# S7_Audio.net
KiCad netlist of a schematic drawn in Altium Designer
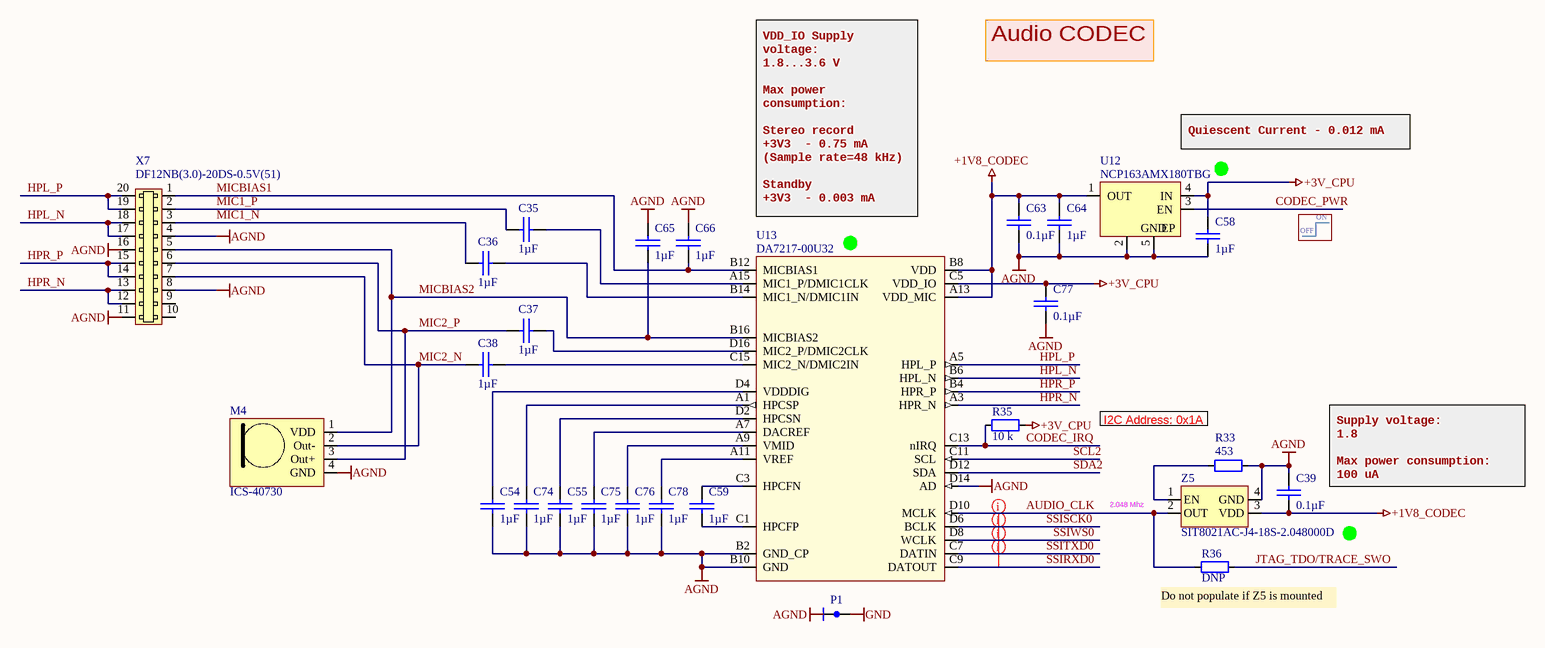
[diagram p0: S7_Audio.SchDoc]

(export (version "E")
  (design (tool "Eeschema 10.0.6"))
  (components
    (comp (ref "C35")
      (value "1µF")
      (footprint "0402 CAP")
      (description "1µF, ±20%, 25V, X5R, 0402 (1005 Metric), -55°C ~ 85°C, -, General Purpose")
      (fields (field (name "PART NUMBER") "TMK105BJ105MV-F") (field (name "MANUFACTURER") "Taiyo Yuden"))
      (libsource (lib "ea_PassivComps") (part "Capacitor"))
    )
    (comp (ref "C36")
      (value "1µF")
      (footprint "0402 CAP")
      (description "1µF, ±20%, 25V, X5R, 0402 (1005 Metric), -55°C ~ 85°C, -, General Purpose")
      (fields (field (name "PART NUMBER") "TMK105BJ105MV-F") (field (name "MANUFACTURER") "Taiyo Yuden"))
      (libsource (lib "ea_PassivComps") (part "Capacitor"))
    )
    (comp (ref "C37")
      (value "1µF")
      (footprint "0402 CAP")
      (description "1µF, ±20%, 25V, X5R, 0402 (1005 Metric), -55°C ~ 85°C, -, General Purpose")
      (fields (field (name "PART NUMBER") "TMK105BJ105MV-F") (field (name "MANUFACTURER") "Taiyo Yuden"))
      (libsource (lib "ea_PassivComps") (part "Capacitor"))
    )
    (comp (ref "C38")
      (value "1µF")
      (footprint "0402 CAP")
      (description "1µF, ±20%, 25V, X5R, 0402 (1005 Metric), -55°C ~ 85°C, -, General Purpose")
      (fields (field (name "PART NUMBER") "TMK105BJ105MV-F") (field (name "MANUFACTURER") "Taiyo Yuden"))
      (libsource (lib "ea_PassivComps") (part "Capacitor"))
    )
    (comp (ref "C39")
      (value "0.1µF")
      (footprint "0402 CAP")
      (description "0.1µF, ±10%, 50V, X7R, 0402 (1005 Metric), -55°C ~ 125°C, -, General Purpose")
      (fields
        (field (name "PART NUMBER") "0402B104K500CT")
        (field (name "MANUFACTURER") "Walsin Technology Corporation")
      )
      (libsource (lib "ea_PassivComps") (part "Capacitor"))
    )
    (comp (ref "C54")
      (value "1µF")
      (footprint "0402 CAP")
      (description "1µF, ±20%, 25V, X5R, 0402 (1005 Metric), -55°C ~ 85°C, -, General Purpose")
      (fields (field (name "PART NUMBER") "TMK105BJ105MV-F") (field (name "MANUFACTURER") "Taiyo Yuden"))
      (libsource (lib "ea_PassivComps") (part "Capacitor"))
    )
    (comp (ref "C55")
      (value "1µF")
      (footprint "0402 CAP")
      (description "1µF, ±20%, 25V, X5R, 0402 (1005 Metric), -55°C ~ 85°C, -, General Purpose")
      (fields (field (name "PART NUMBER") "TMK105BJ105MV-F") (field (name "MANUFACTURER") "Taiyo Yuden"))
      (libsource (lib "ea_PassivComps") (part "Capacitor"))
    )
    (comp (ref "C58")
      (value "1µF")
      (footprint "0402 CAP")
      (description "1µF, ±20%, 25V, X5R, 0402 (1005 Metric), -55°C ~ 85°C, -, General Purpose")
      (fields (field (name "PART NUMBER") "TMK105BJ105MV-F") (field (name "MANUFACTURER") "Taiyo Yuden"))
      (libsource (lib "ea_PassivComps") (part "Capacitor"))
    )
    (comp (ref "C59")
      (value "1µF")
      (footprint "0402 CAP")
      (description "1µF, ±20%, 25V, X5R, 0402 (1005 Metric), -55°C ~ 85°C, -, General Purpose")
      (fields (field (name "PART NUMBER") "TMK105BJ105MV-F") (field (name "MANUFACTURER") "Taiyo Yuden"))
      (libsource (lib "ea_PassivComps") (part "Capacitor"))
    )
    (comp (ref "C63")
      (value "0.1µF")
      (footprint "0402 CAP")
      (description "0.1µF, ±10%, 50V, X7R, 0402 (1005 Metric), -55°C ~ 125°C, -, General Purpose")
      (fields
        (field (name "PART NUMBER") "0402B104K500CT")
        (field (name "MANUFACTURER") "Walsin Technology Corporation")
      )
      (libsource (lib "ea_PassivComps") (part "Capacitor"))
    )
    (comp (ref "C64")
      (value "1µF")
      (footprint "0402 CAP")
      (description "1µF, ±20%, 25V, X5R, 0402 (1005 Metric), -55°C ~ 85°C, -, General Purpose")
      (fields (field (name "PART NUMBER") "TMK105BJ105MV-F") (field (name "MANUFACTURER") "Taiyo Yuden"))
      (libsource (lib "ea_PassivComps") (part "Capacitor"))
    )
    (comp (ref "C65")
      (value "1µF")
      (footprint "0402 CAP")
      (description "1µF, ±20%, 25V, X5R, 0402 (1005 Metric), -55°C ~ 85°C, -, General Purpose")
      (fields (field (name "PART NUMBER") "TMK105BJ105MV-F") (field (name "MANUFACTURER") "Taiyo Yuden"))
      (libsource (lib "ea_PassivComps") (part "Capacitor"))
    )
    (comp (ref "C66")
      (value "1µF")
      (footprint "0402 CAP")
      (description "1µF, ±20%, 25V, X5R, 0402 (1005 Metric), -55°C ~ 85°C, -, General Purpose")
      (fields (field (name "PART NUMBER") "TMK105BJ105MV-F") (field (name "MANUFACTURER") "Taiyo Yuden"))
      (libsource (lib "ea_PassivComps") (part "Capacitor"))
    )
    (comp (ref "C74")
      (value "1µF")
      (footprint "0402 CAP")
      (description "1µF, ±20%, 25V, X5R, 0402 (1005 Metric), -55°C ~ 85°C, -, General Purpose")
      (fields (field (name "PART NUMBER") "TMK105BJ105MV-F") (field (name "MANUFACTURER") "Taiyo Yuden"))
      (libsource (lib "ea_PassivComps") (part "Capacitor"))
    )
    (comp (ref "C75")
      (value "1µF")
      (footprint "0402 CAP")
      (description "1µF, ±20%, 25V, X5R, 0402 (1005 Metric), -55°C ~ 85°C, -, General Purpose")
      (fields (field (name "PART NUMBER") "TMK105BJ105MV-F") (field (name "MANUFACTURER") "Taiyo Yuden"))
      (libsource (lib "ea_PassivComps") (part "Capacitor"))
    )
    (comp (ref "C76")
      (value "1µF")
      (footprint "0402 CAP")
      (description "1µF, ±20%, 25V, X5R, 0402 (1005 Metric), -55°C ~ 85°C, -, General Purpose")
      (fields (field (name "PART NUMBER") "TMK105BJ105MV-F") (field (name "MANUFACTURER") "Taiyo Yuden"))
      (libsource (lib "ea_PassivComps") (part "Capacitor"))
    )
    (comp (ref "C77")
      (value "0.1µF")
      (footprint "0402 CAP")
      (description "0.1µF, ±10%, 50V, X7R, 0402 (1005 Metric), -55°C ~ 125°C, -, General Purpose")
      (fields
        (field (name "PART NUMBER") "0402B104K500CT")
        (field (name "MANUFACTURER") "Walsin Technology Corporation")
      )
      (libsource (lib "ea_PassivComps") (part "Capacitor"))
    )
    (comp (ref "C78")
      (value "1µF")
      (footprint "0402 CAP")
      (description "1µF, ±20%, 25V, X5R, 0402 (1005 Metric), -55°C ~ 85°C, -, General Purpose")
      (fields (field (name "PART NUMBER") "TMK105BJ105MV-F") (field (name "MANUFACTURER") "Taiyo Yuden"))
      (libsource (lib "ea_PassivComps") (part "Capacitor"))
    )
    (comp (ref "M4")
      (value "ICS-40730")
      (footprint "ICS-40730")
      (fields (field (name "MANUFACTURER") "TDK InvenSense") (field (name "PARTNUM") "1428-1141-1-ND"))
      (libsource (lib "ea_Sound_devices") (part "ICS-40730"))
    )
    (comp (ref "P1")
      (value "Net tie 0.1mm")
      (footprint "Net tee 0.1 mm")
      (libsource (lib "ea_Mechanical") (part "Net tie 0.1mm"))
    )
    (comp (ref "R33")
      (value "453")
      (footprint "0402")
      (fields
        (field (name "MANUFACTURER") "Stackpole Electronics Inc")
        (field (name "TOLERANCE") "±1%")
        (field (name "VOLTAGE") "75V")
      )
      (libsource (lib "ea_PassivComps") (part "Resistor"))
    )
    (comp (ref "R35")
      (value "10 k")
      (footprint "0402")
      (fields
        (field (name "MANUFACTURER") "Stackpole Electronics Inc")
        (field (name "TOLERANCE") "±1%")
        (field (name "VOLTAGE") "75V")
      )
      (libsource (lib "") (part "Resistor_1"))
    )
    (comp (ref "R36")
      (value "DNP")
      (footprint "0402")
      (fields (field (name "Comment") "Resistor"))
      (libsource (lib "ea_PassivComps") (part "Resistor"))
    )
    (comp (ref "U12")
      (value "NCP163AMX180TBG")
      (footprint "4-XDFN")
      (description "LDO 1.8V, 250 mA, Vin < 5.5V, Iq < 20uA, -40..+125 C,  4-XDFN (1x1)")
      (fields
        (field (name "MANUFACTURER") "ON Semiconductor")
        (field (name "PARTNUM") "NCP163AMX180TBGOSCT-ND")
      )
      (libsource (lib "ea_IC_Linear_reg_LDO") (part "NCP163AMX180TBG"))
    )
    (comp (ref "U13")
      (value "DA7217-00U32")
      (footprint "Dilaog 34-WLCSP (4.57x1.98)")
      (description "Low power CODEC, 24 b, 2/2, I²C, I²S,  1.5V ~ 3.6V,  -25°C ~ 85°C, 34-WLCSP (4.57x1.98)")
      (fields
        (field (name "MANUFACTURER") "Dialog Semiconductor GmbH")
        (field (name "PARTNUM") "1564-1043-1-ND")
      )
      (libsource (lib "ea_IC_audio") (part "DA7217-00U32"))
    )
    (comp (ref "X7")
      (value "DF12NB(3.0)-20DS-0.5V(51)")
      (footprint "DF12NB(3.0)-20DS-0.5V(51)")
      (fields
        (field (name "MANUFACTURER") "Hirose Electric")
        (field (name "PARTNUM") "26-DF12NB(3.0)-20DS-0.5V(51)CT-ND - Cut Tape (CT)")
      )
      (libsource (lib "ea_Connectors_0.5_mm_pitch") (part "DF12NB(3.0)-20DS-0.5V(51)"))
    )
    (comp (ref "Z5")
      (value "SIT8021AC-J4-18S-2.048000D")
      (footprint "SiT8021")
      (description "2.048MHz XO (Standard) LVCMOS Oscillator 1.8V Standby (Power Down) 4-UFBGA, CSPBGA, -20...+70 C")
      (fields (field (name "MANUFACTURER") "SiTIME"))
      (libsource (lib "ea_OSC_CLK_GEN") (part "SIT8021AC-J4-18S-2.048000D"))
    )
  )
  (nets
    (net (code "1") (name "+1V8_CODEC") (class "Default")
      (node (ref "C39") (pin "2") (pinfunction "2_2") (pintype "passive"))
      (node (ref "C63") (pin "1") (pinfunction "1_1") (pintype "passive"))
      (node (ref "C64") (pin "1") (pinfunction "1_1") (pintype "passive"))
      (node (ref "U12") (pin "1") (pinfunction "OUT_1") (pintype "power_in"))
      (node (ref "U13") (pin "A13") (pinfunction "VDD_MIC_A13") (pintype "power_in"))
      (node (ref "U13") (pin "B8") (pinfunction "VDD_B8") (pintype "power_in"))
      (node (ref "Z5") (pin "3") (pinfunction "VDD_3") (pintype "passive"))
    )
    (net (code "2") (name "+3V_CPU") (class "Default")
      (node (ref "C58") (pin "1") (pinfunction "1_1") (pintype "passive"))
      (node (ref "C77") (pin "1") (pinfunction "1_1") (pintype "passive"))
      (node (ref "R35") (pin "2") (pinfunction "2_2") (pintype "passive"))
      (node (ref "U12") (pin "4") (pinfunction "IN_4") (pintype "power_in"))
      (node (ref "U13") (pin "C5") (pinfunction "VDD_IO_C5") (pintype "power_in"))
    )
    (net (code "3") (name "/AUDIO_CLK") (class "Default")
      (node (ref "R36") (pin "2") (pinfunction "2_2") (pintype "passive"))
      (node (ref "U13") (pin "D10") (pinfunction "MCLK_D10") (pintype "input"))
      (node (ref "Z5") (pin "2") (pinfunction "OUT_2") (pintype "passive"))
    )
    (net (code "4") (name "/CODEC_IRQ") (class "Default")
      (node (ref "R35") (pin "1") (pinfunction "1_1") (pintype "passive"))
      (node (ref "U13") (pin "C13") (pinfunction "nIRQ_C13") (pintype "bidirectional"))
    )
    (net (code "5") (name "/CODEC_PWR") (class "Default")
      (node (ref "U12") (pin "3") (pinfunction "EN_3") (pintype "power_in"))
    )
    (net (code "6") (name "/HPL_N") (class "Default")
      (node (ref "U13") (pin "B6") (pinfunction "HPL_N_B6") (pintype "output"))
      (node (ref "X7") (pin "17") (pinfunction "9_17") (pintype "passive"))
      (node (ref "X7") (pin "18") (pinfunction "10_18") (pintype "passive"))
    )
    (net (code "7") (name "/HPL_P") (class "Default")
      (node (ref "U13") (pin "A5") (pinfunction "HPL_P_A5") (pintype "output"))
      (node (ref "X7") (pin "19") (pinfunction "10_19") (pintype "passive"))
      (node (ref "X7") (pin "20") (pinfunction "11_20") (pintype "passive"))
    )
    (net (code "8") (name "/HPR_N") (class "Default")
      (node (ref "U13") (pin "A3") (pinfunction "HPR_N_A3") (pintype "output"))
      (node (ref "X7") (pin "12") (pinfunction "7_12") (pintype "passive"))
      (node (ref "X7") (pin "13") (pinfunction "7_13") (pintype "passive"))
    )
    (net (code "9") (name "/HPR_P") (class "Default")
      (node (ref "U13") (pin "B4") (pinfunction "HPR_P_B4") (pintype "output"))
      (node (ref "X7") (pin "14") (pinfunction "8_14") (pintype "passive"))
      (node (ref "X7") (pin "15") (pinfunction "8_15") (pintype "passive"))
    )
    (net (code "10") (name "/JTAG_TDO{slash}TRACE_SWO") (class "Default")
      (node (ref "R36") (pin "1") (pinfunction "1_1") (pintype "passive"))
    )
    (net (code "11") (name "/MIC1_N") (class "Default")
      (node (ref "C36") (pin "1") (pinfunction "1_1") (pintype "passive"))
      (node (ref "X7") (pin "3") (pinfunction "2_3") (pintype "passive"))
    )
    (net (code "12") (name "/MIC1_P") (class "Default")
      (node (ref "C35") (pin "1") (pinfunction "1_1") (pintype "passive"))
      (node (ref "X7") (pin "2") (pinfunction "2_2") (pintype "passive"))
    )
    (net (code "13") (name "/MIC2_N") (class "Default")
      (node (ref "C38") (pin "1") (pinfunction "1_1") (pintype "passive"))
      (node (ref "M4") (pin "2") (pinfunction "Out-_2") (pintype "passive"))
      (node (ref "X7") (pin "7") (pinfunction "4_7") (pintype "passive"))
    )
    (net (code "14") (name "/MIC2_P") (class "Default")
      (node (ref "C37") (pin "1") (pinfunction "1_1") (pintype "passive"))
      (node (ref "M4") (pin "3") (pinfunction "Out+_3") (pintype "passive"))
      (node (ref "X7") (pin "6") (pinfunction "4_6") (pintype "passive"))
    )
    (net (code "15") (name "/MICBIAS1") (class "Default")
      (node (ref "C66") (pin "2") (pinfunction "2_2") (pintype "passive"))
      (node (ref "U13") (pin "B12") (pinfunction "MICBIAS1_B12") (pintype "bidirectional"))
      (node (ref "X7") (pin "1") (pinfunction "1_1") (pintype "passive"))
    )
    (net (code "16") (name "/MICBIAS2") (class "Default")
      (node (ref "C65") (pin "2") (pinfunction "2_2") (pintype "passive"))
      (node (ref "M4") (pin "1") (pinfunction "VDD_1") (pintype "passive"))
      (node (ref "U13") (pin "B16") (pinfunction "MICBIAS2_B16") (pintype "bidirectional"))
      (node (ref "X7") (pin "5") (pinfunction "3_5") (pintype "passive"))
    )
    (net (code "17") (name "/SCL2") (class "Default")
      (node (ref "U13") (pin "C11") (pinfunction "SCL_C11") (pintype "input"))
    )
    (net (code "18") (name "/SDA2") (class "Default")
      (node (ref "U13") (pin "D12") (pinfunction "SDA_D12") (pintype "bidirectional"))
    )
    (net (code "19") (name "/SSIRXD0") (class "Default")
      (node (ref "U13") (pin "C9") (pinfunction "DATOUT_C9") (pintype "bidirectional"))
    )
    (net (code "20") (name "/SSISCK0") (class "Default")
      (node (ref "U13") (pin "D6") (pinfunction "BCLK_D6") (pintype "bidirectional"))
    )
    (net (code "21") (name "/SSITXD0") (class "Default")
      (node (ref "U13") (pin "C7") (pinfunction "DATIN_C7") (pintype "bidirectional"))
    )
    (net (code "22") (name "/SSIWS0") (class "Default")
      (node (ref "U13") (pin "D8") (pinfunction "WCLK_D8") (pintype "bidirectional"))
    )
    (net (code "23") (name "AGND") (class "Default")
      (node (ref "C39") (pin "1") (pinfunction "1_1") (pintype "passive"))
      (node (ref "C54") (pin "2") (pinfunction "2_2") (pintype "passive"))
      (node (ref "C55") (pin "2") (pinfunction "2_2") (pintype "passive"))
      (node (ref "C58") (pin "2") (pinfunction "2_2") (pintype "passive"))
      (node (ref "C63") (pin "2") (pinfunction "2_2") (pintype "passive"))
      (node (ref "C64") (pin "2") (pinfunction "2_2") (pintype "passive"))
      (node (ref "C65") (pin "1") (pinfunction "1_1") (pintype "passive"))
      (node (ref "C66") (pin "1") (pinfunction "1_1") (pintype "passive"))
      (node (ref "C74") (pin "2") (pinfunction "2_2") (pintype "passive"))
      (node (ref "C75") (pin "2") (pinfunction "2_2") (pintype "passive"))
      (node (ref "C76") (pin "2") (pinfunction "2_2") (pintype "passive"))
      (node (ref "C77") (pin "2") (pinfunction "2_2") (pintype "passive"))
      (node (ref "C78") (pin "2") (pinfunction "2_2") (pintype "passive"))
      (node (ref "M4") (pin "4") (pinfunction "GND_4") (pintype "passive"))
      (node (ref "P1") (pin "1") (pinfunction "1_1") (pintype "passive"))
      (node (ref "R33") (pin "1") (pinfunction "1_1") (pintype "passive"))
      (node (ref "U12") (pin "2") (pinfunction "GND_2") (pintype "power_in"))
      (node (ref "U12") (pin "5") (pinfunction "EP_5") (pintype "power_in"))
      (node (ref "U13") (pin "B10") (pinfunction "GND_B10") (pintype "power_in"))
      (node (ref "U13") (pin "B2") (pinfunction "GND_CP_B2") (pintype "power_in"))
      (node (ref "U13") (pin "D14") (pinfunction "AD_D14") (pintype "input"))
      (node (ref "X7") (pin "11") (pinfunction "6_11") (pintype "passive"))
      (node (ref "X7") (pin "16") (pinfunction "9_16") (pintype "passive"))
      (node (ref "X7") (pin "4") (pinfunction "3_4") (pintype "passive"))
      (node (ref "X7") (pin "8") (pinfunction "5_8") (pintype "passive"))
      (node (ref "Z5") (pin "4") (pinfunction "GND_4") (pintype "passive"))
    )
    (net (code "24") (name "GND") (class "Default")
      (node (ref "P1") (pin "2") (pinfunction "2_2") (pintype "passive"))
    )
    (net (code "25") (name "Net-(U13-DACREF)") (class "Default")
      (node (ref "C75") (pin "1") (pinfunction "1_1") (pintype "passive"))
      (node (ref "U13") (pin "A7") (pinfunction "DACREF_A7") (pintype "power_in"))
    )
    (net (code "26") (name "Net-(U13-HPCFN)") (class "Default")
      (node (ref "C59") (pin "1") (pinfunction "1_1") (pintype "passive"))
      (node (ref "U13") (pin "C3") (pinfunction "HPCFN_C3") (pintype "bidirectional"))
    )
    (net (code "27") (name "Net-(U13-HPCFP)") (class "Default")
      (node (ref "C59") (pin "2") (pinfunction "2_2") (pintype "passive"))
      (node (ref "U13") (pin "C1") (pinfunction "HPCFP_C1") (pintype "bidirectional"))
    )
    (net (code "28") (name "Net-(U13-HPCSN)") (class "Default")
      (node (ref "C55") (pin "1") (pinfunction "1_1") (pintype "passive"))
      (node (ref "U13") (pin "D2") (pinfunction "HPCSN_D2") (pintype "bidirectional"))
    )
    (net (code "29") (name "Net-(U13-HPCSP)") (class "Default")
      (node (ref "C74") (pin "1") (pinfunction "1_1") (pintype "passive"))
      (node (ref "U13") (pin "A1") (pinfunction "HPCSP_A1") (pintype "output"))
    )
    (net (code "30") (name "Net-(U13-MIC1_N{slash}DMIC1IN)") (class "Default")
      (node (ref "C36") (pin "2") (pinfunction "2_2") (pintype "passive"))
      (node (ref "U13") (pin "B14") (pinfunction "MIC1_N/DMIC1IN_B14") (pintype "bidirectional"))
    )
    (net (code "31") (name "Net-(U13-MIC1_P{slash}DMIC1CLK)") (class "Default")
      (node (ref "C35") (pin "2") (pinfunction "2_2") (pintype "passive"))
      (node (ref "U13") (pin "A15") (pinfunction "MIC1_P/DMIC1CLK_A15") (pintype "bidirectional"))
    )
    (net (code "32") (name "Net-(U13-MIC2_N{slash}DMIC2IN)") (class "Default")
      (node (ref "C38") (pin "2") (pinfunction "2_2") (pintype "passive"))
      (node (ref "U13") (pin "C15") (pinfunction "MIC2_N/DMIC2IN_C15") (pintype "bidirectional"))
    )
    (net (code "33") (name "Net-(U13-MIC2_P{slash}DMIC2CLK)") (class "Default")
      (node (ref "C37") (pin "2") (pinfunction "2_2") (pintype "passive"))
      (node (ref "U13") (pin "D16") (pinfunction "MIC2_P/DMIC2CLK_D16") (pintype "bidirectional"))
    )
    (net (code "34") (name "Net-(U13-VDDDIG)") (class "Default")
      (node (ref "C54") (pin "1") (pinfunction "1_1") (pintype "passive"))
      (node (ref "U13") (pin "D4") (pinfunction "VDDDIG_D4") (pintype "power_in"))
    )
    (net (code "35") (name "Net-(U13-VMID)") (class "Default")
      (node (ref "C76") (pin "1") (pinfunction "1_1") (pintype "passive"))
      (node (ref "U13") (pin "A9") (pinfunction "VMID_A9") (pintype "power_in"))
    )
    (net (code "36") (name "Net-(U13-VREF)") (class "Default")
      (node (ref "C78") (pin "1") (pinfunction "1_1") (pintype "passive"))
      (node (ref "U13") (pin "A11") (pinfunction "VREF_A11") (pintype "power_in"))
    )
    (net (code "37") (name "Net-(Z5-EN)") (class "Default")
      (node (ref "R33") (pin "2") (pinfunction "2_2") (pintype "passive"))
      (node (ref "Z5") (pin "1") (pinfunction "EN_1") (pintype "passive"))
    )
    (net (code "38") (name "unconnected-(X7-5-Pad9)") (class "Default")
      (node (ref "X7") (pin "9") (pinfunction "5_9") (pintype "passive"))
    )
    (net (code "39") (name "unconnected-(X7-6-Pad10)") (class "Default")
      (node (ref "X7") (pin "10") (pinfunction "6_10") (pintype "passive"))
    )
  )
)
